# Sheet1.net
KiCad netlist of a schematic drawn in Altium Designer
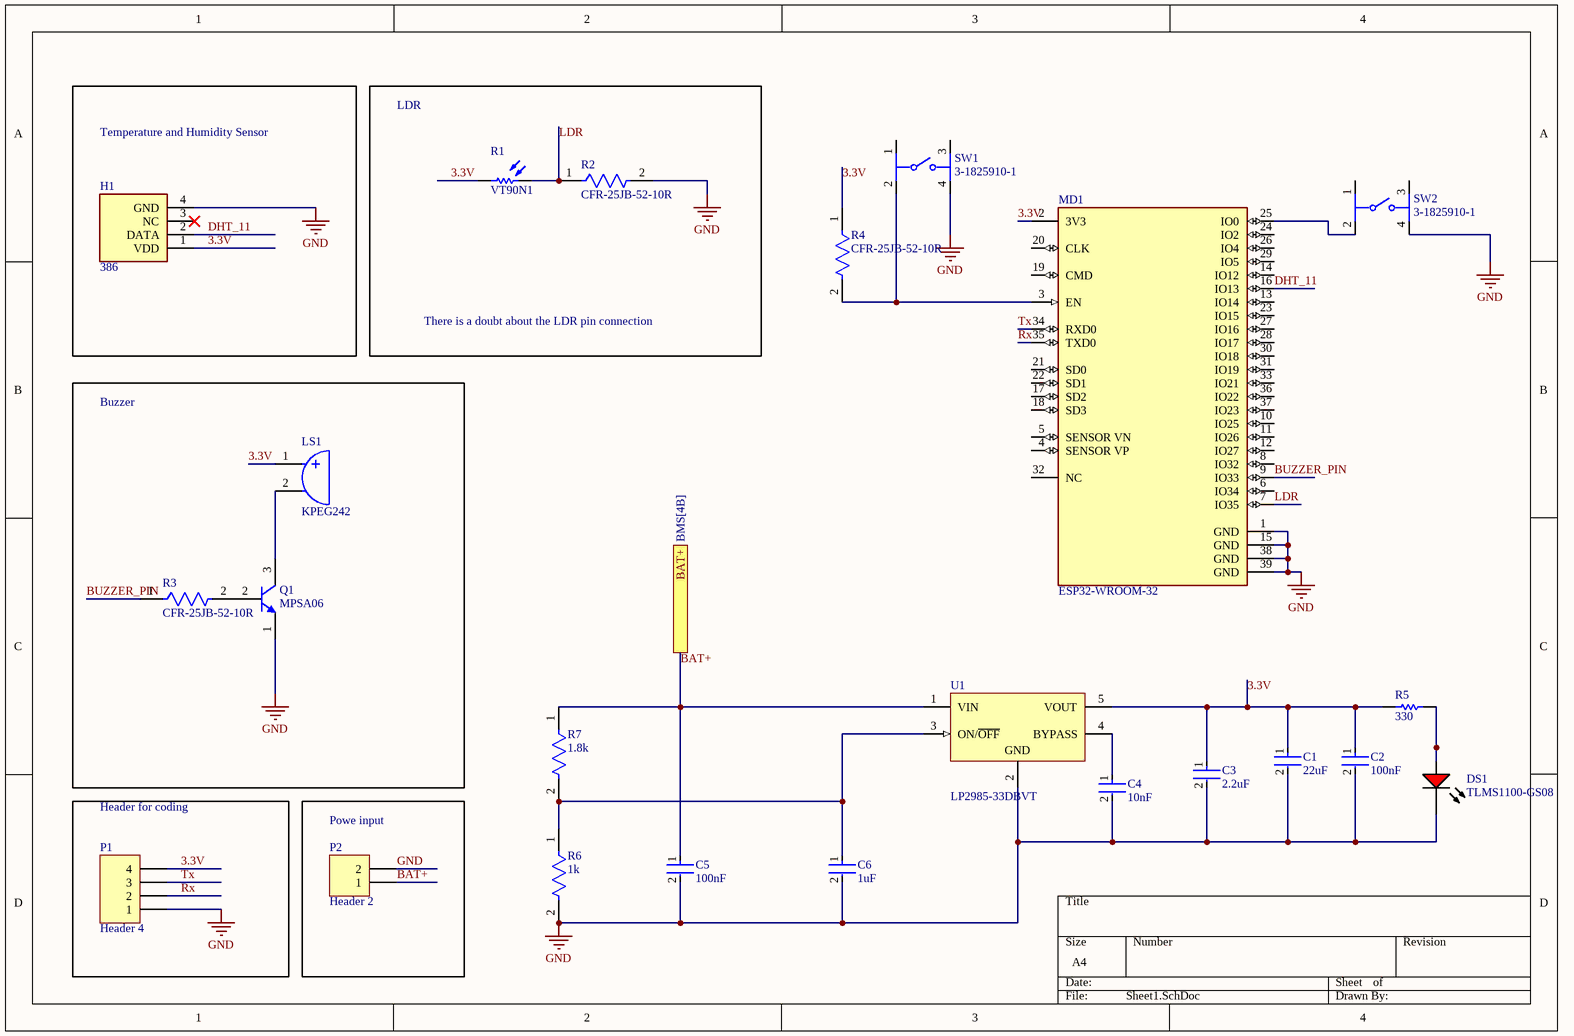
[diagram p0: Sheet1.SchDoc]

(export (version "E")
  (design (tool "Eeschema 10.0.6"))
  (components
    (comp (ref "C1")
      (value "22uF")
      (footprint "FP-GCM188-0_1-IPC_A")
      (description "Ceramic Capacitor for Automotive 100nF  ±10% 25VDC X8R 0603 Paper T/R")
      (fields (field (name "TOLERANCE") "10%"))
      (libsource (lib "Altium Content Vault") (part "02cd4be3c70576c341d710602a673aa"))
    )
    (comp (ref "C2")
      (value "100nF")
      (footprint "FP-GCM188-0_1-IPC_A")
      (description "Ceramic Capacitor for Automotive 100nF  ±10% 25VDC X8R 0603 Paper T/R")
      (fields (field (name "TOLERANCE") "10%"))
      (libsource (lib "Altium Content Vault") (part "02cd4be3c70576c341d710602a673aa"))
    )
    (comp (ref "C3")
      (value "2.2uF")
      (footprint "FP-GCM188-0_1-IPC_A")
      (description "Ceramic Capacitor for Automotive 100nF  ±10% 25VDC X8R 0603 Paper T/R")
      (fields (field (name "TOLERANCE") "10%"))
      (libsource (lib "Altium Content Vault") (part "02cd4be3c70576c341d710602a673aa"))
    )
    (comp (ref "C4")
      (value "10nF")
      (footprint "FP-GCM188-0_1-IPC_A")
      (description "Ceramic Capacitor for Automotive 100nF  ±10% 25VDC X8R 0603 Paper T/R")
      (fields (field (name "TOLERANCE") "10%"))
      (libsource (lib "Altium Content Vault") (part "02cd4be3c70576c341d710602a673aa"))
    )
    (comp (ref "C5")
      (value "100nF")
      (footprint "FP-GCM188-0_1-IPC_A")
      (description "Ceramic Capacitor for Automotive 100nF  ±10% 25VDC X8R 0603 Paper T/R")
      (fields (field (name "TOLERANCE") "10%"))
      (libsource (lib "Altium Content Vault") (part "02cd4be3c70576c341d710602a673aa"))
    )
    (comp (ref "C6")
      (value "1uF")
      (footprint "FP-GCM188-0_1-IPC_A")
      (description "Ceramic Capacitor for Automotive 100nF  ±10% 25VDC X8R 0603 Paper T/R")
      (fields (field (name "TOLERANCE") "10%"))
      (libsource (lib "Altium Content Vault") (part "02cd4be3c70576c341d710602a673aa"))
    )
    (comp (ref "DS1")
      (value "TLMS1100-GS08")
      (footprint "VISH-TLMX1100_V")
      (description "LED, RED, 2.1 V, -40 to 100 degC, 2-Pin SMD (0603), RoHS, Tape and Reel")
      (fields (field (name "TOLERANCE") "5%"))
      (libsource (lib "Altium Content Vault") (part "LED-RED-AK-2"))
    )
    (comp (ref "H1")
      (value "386")
      (footprint "SamacSys:386")
      (description "Hardware")
      (fields (field (name "MOUSER PART NUMBER") "485-386"))
      (libsource (lib "*") (part "386"))
    )
    (comp (ref "LS1")
      (value "KPEG242")
      (footprint "KINGS-KPEG242-2")
      (description "Piezo Indicator, 4100 Hz, 3 to 16 V, -20 to 70 degC, 2-Pin THD, RoHS")
      (fields (field (name "PARTNUMBER") "KPE-242") (field (name "MANUFACTURER") "KingstateElectronicsCorp."))
      (libsource (lib "Altium Content Vault") (part "KINGS-KPEG242-2"))
    )
    (comp (ref "MD1")
      (value "ESP32-WROOM-32")
      (footprint "FP-ESP32-WROOM-32-MFG")
      (description "RX TXRX MOD WIFI SURFACE MOUNT")
      (libsource (lib "Altium Content Vault") (part "ee866abf0b6c51247b7f5cdebf2f250"))
    )
    (comp (ref "P1")
      (value "Header 4")
      (footprint "HDR1X4")
      (description "Header, 4-Pin")
      (fields (field (name "PUBLISHER") "Altium Limited"))
      (libsource (lib "Miscellaneous Connectors") (part "Header 4"))
    )
    (comp (ref "P2")
      (value "Header 2")
      (footprint "HDR1X2")
      (description "Header, 2-Pin")
      (fields (field (name "PUBLISHER") "Altium Limited"))
      (libsource (lib "Miscellaneous Connectors") (part "Header 2"))
    )
    (comp (ref "Q1")
      (value "MPSA06")
      (footprint "ONSC-TO-92-3-29-11")
      (description "Amplifier Transistor, 3-Pin TO-92, Bulk Box")
      (fields (field (name "MANUFACTURER") "On Semiconductor"))
      (libsource (lib "Altium Content Vault") (part "ONSC-NPN-E1B2C3-3"))
    )
    (comp (ref "R1")
      (value "VT90N1")
      (footprint "EXCE-VT90N1")
      (description "Photoconductive Resistor, 200 kOhm, 100 V, 80 mW, -40 to 75 degC, 2-Pin THD, RoHS")
      (fields (field (name "MANUFACTURER") "Excelitas Technology"))
      (libsource (lib "Altium Content Vault") (part "PHOTO-RES-2"))
    )
    (comp (ref "R2")
      (value "CFR-25JB-52-10R")
      (footprint "FP-CFR-25-MFG")
      (description "RES 10 OHM 1/4W 5% AXIAL")
      (fields (field (name "TOLERANCE") "5%"))
      (libsource (lib "Altium Content Vault") (part "1029c3af85768c4190bb7ad29bc67b5"))
    )
    (comp (ref "R3")
      (value "CFR-25JB-52-10R")
      (footprint "FP-CFR-25-MFG")
      (description "RES 10 OHM 1/4W 5% AXIAL")
      (fields (field (name "TOLERANCE") "5%"))
      (libsource (lib "Altium Content Vault") (part "1029c3af85768c4190bb7ad29bc67b5"))
    )
    (comp (ref "R4")
      (value "CFR-25JB-52-10R")
      (footprint "FP-CFR-25-MFG")
      (description "RES 10 OHM 1/4W 5% AXIAL")
      (fields (field (name "TOLERANCE") "5%"))
      (libsource (lib "Altium Content Vault") (part "1029c3af85768c4190bb7ad29bc67b5"))
    )
    (comp (ref "R5")
      (value "330")
      (footprint "RESC1608X55X25NL10T15")
      (description "Chip Resistor, 330 Ohm, +/- 1%, 0.1 W, -55 to 155 degC, 0603 (1608 Metric), RoHS, Tape and Reel")
      (fields (field (name "TOLERANCE") "10%"))
      (libsource (lib "Altium Content Vault") (part "RES-2"))
    )
    (comp (ref "R6")
      (value "1k")
      (footprint "FP-RC0603-0_55-IPC_C")
      (description "RES SMD 1.8K OHM 1% 1/10W 0603")
      (fields (field (name "TOLERANCE") "1%"))
      (libsource (lib "Altium Content Vault") (part "1029c3af85768c4190bb7ad29bc67b5"))
    )
    (comp (ref "R7")
      (value "1.8k")
      (footprint "FP-RC0603-0_55-IPC_C")
      (description "RES SMD 1.8K OHM 1% 1/10W 0603")
      (fields (field (name "TOLERANCE") "1%"))
      (libsource (lib "Altium Content Vault") (part "1029c3af85768c4190bb7ad29bc67b5"))
    )
    (comp (ref "SW1")
      (value "3-1825910-1")
      (footprint "FP-3-1825910-1-MFG")
      (description "SWITCH TACTILE SPST-NO 0.05A 24V")
      (fields
        (field (name "MANUFACTURER") "TE Connectivity")
        (field (name "OCTOPART") "https://octopart.com/3-1825910-1-te+connectivity-46506874")
      )
      (libsource (lib "Altium Content Vault") (part "b8895f3f4cefb76e1819d2863dba89b"))
    )
    (comp (ref "SW2")
      (value "3-1825910-1")
      (footprint "FP-3-1825910-1-MFG")
      (description "SWITCH TACTILE SPST-NO 0.05A 24V")
      (fields
        (field (name "MANUFACTURER") "TE Connectivity")
        (field (name "OCTOPART") "https://octopart.com/3-1825910-1-te+connectivity-46506874")
      )
      (libsource (lib "Altium Content Vault") (part "b8895f3f4cefb76e1819d2863dba89b"))
    )
    (comp (ref "U1")
      (value "LP2985-33DBVT")
      (footprint "DBV0005A_L")
      (fields (field (name "MANUFACTURER") "Texas Instruments"))
      (libsource (lib "Altium Content Vault") (part "TI-LP2985_A-10DBV5"))
    )
  )
  (nets
    (net (code "1") (name "/3.3V") (class "Default")
      (node (ref "C1") (pin "1") (pinfunction "1_1") (pintype "passive"))
      (node (ref "C2") (pin "1") (pinfunction "1_1") (pintype "passive"))
      (node (ref "C3") (pin "1") (pinfunction "1_1") (pintype "passive"))
      (node (ref "H1") (pin "1") (pinfunction "VDD_1") (pintype "passive"))
      (node (ref "LS1") (pin "1") (pinfunction "1_1") (pintype "passive"))
      (node (ref "MD1") (pin "2") (pinfunction "3V3_2") (pintype "power_in"))
      (node (ref "P1") (pin "4") (pinfunction "4_4") (pintype "passive"))
      (node (ref "R1") (pin "1") (pinfunction "1_1") (pintype "passive"))
      (node (ref "R4") (pin "1") (pinfunction "1_1") (pintype "passive"))
      (node (ref "R5") (pin "1") (pinfunction "1_1") (pintype "passive"))
      (node (ref "U1") (pin "5") (pinfunction "VOUT_5") (pintype "power_in"))
    )
    (net (code "2") (name "/BAT+") (class "Default")
      (node (ref "C5") (pin "1") (pinfunction "1_1") (pintype "passive"))
      (node (ref "P2") (pin "1") (pinfunction "1_1") (pintype "passive"))
      (node (ref "R7") (pin "1") (pinfunction "1_1") (pintype "passive"))
      (node (ref "U1") (pin "1") (pinfunction "VIN_1") (pintype "power_in"))
    )
    (net (code "3") (name "/BUZZER_PIN") (class "Default")
      (node (ref "MD1") (pin "9") (pinfunction "IO33_9") (pintype "bidirectional"))
      (node (ref "R3") (pin "1") (pinfunction "1_1") (pintype "passive"))
    )
    (net (code "4") (name "/DHT_11") (class "Default")
      (node (ref "H1") (pin "2") (pinfunction "DATA_2") (pintype "passive"))
      (node (ref "MD1") (pin "16") (pinfunction "IO13_16") (pintype "bidirectional"))
    )
    (net (code "5") (name "/LDR") (class "Default")
      (node (ref "MD1") (pin "7") (pinfunction "IO35_7") (pintype "bidirectional"))
      (node (ref "R1") (pin "2") (pinfunction "2_2") (pintype "passive"))
      (node (ref "R2") (pin "1") (pinfunction "1_1") (pintype "passive"))
    )
    (net (code "6") (name "/Rx") (class "Default")
      (node (ref "MD1") (pin "35") (pinfunction "TXD0_35") (pintype "bidirectional"))
      (node (ref "P1") (pin "2") (pinfunction "2_2") (pintype "passive"))
    )
    (net (code "7") (name "/Tx") (class "Default")
      (node (ref "MD1") (pin "34") (pinfunction "RXD0_34") (pintype "bidirectional"))
      (node (ref "P1") (pin "3") (pinfunction "3_3") (pintype "passive"))
    )
    (net (code "8") (name "GND") (class "Default")
      (node (ref "C1") (pin "2") (pinfunction "2_2") (pintype "passive"))
      (node (ref "C2") (pin "2") (pinfunction "2_2") (pintype "passive"))
      (node (ref "C3") (pin "2") (pinfunction "2_2") (pintype "passive"))
      (node (ref "C4") (pin "2") (pinfunction "2_2") (pintype "passive"))
      (node (ref "C5") (pin "2") (pinfunction "2_2") (pintype "passive"))
      (node (ref "C6") (pin "2") (pinfunction "2_2") (pintype "passive"))
      (node (ref "DS1") (pin "2") (pinfunction "K_2") (pintype "passive"))
      (node (ref "H1") (pin "4") (pinfunction "GND_4") (pintype "passive"))
      (node (ref "MD1") (pin "1") (pinfunction "GND_1") (pintype "power_in"))
      (node (ref "MD1") (pin "15") (pinfunction "GND_15") (pintype "power_in"))
      (node (ref "MD1") (pin "38") (pinfunction "GND_38") (pintype "power_in"))
      (node (ref "MD1") (pin "39") (pinfunction "GND_39") (pintype "power_in"))
      (node (ref "P1") (pin "1") (pinfunction "1_1") (pintype "passive"))
      (node (ref "P2") (pin "2") (pinfunction "2_2") (pintype "passive"))
      (node (ref "Q1") (pin "1") (pinfunction "E_1") (pintype "passive"))
      (node (ref "R2") (pin "2") (pinfunction "2_2") (pintype "passive"))
      (node (ref "R6") (pin "2") (pinfunction "2_2") (pintype "passive"))
      (node (ref "SW1") (pin "4") (pinfunction "4_4") (pintype "passive"))
      (node (ref "SW2") (pin "4") (pinfunction "4_4") (pintype "passive"))
      (node (ref "U1") (pin "2") (pinfunction "GND_2") (pintype "power_in"))
    )
    (net (code "9") (name "Net-(DS1-A)") (class "Default")
      (node (ref "DS1") (pin "1") (pinfunction "A_1") (pintype "passive"))
      (node (ref "R5") (pin "2") (pinfunction "2_2") (pintype "passive"))
    )
    (net (code "10") (name "Net-(MD1-EN)") (class "Default")
      (node (ref "MD1") (pin "3") (pinfunction "EN_3") (pintype "input"))
      (node (ref "R4") (pin "2") (pinfunction "2_2") (pintype "passive"))
      (node (ref "SW1") (pin "2") (pinfunction "2_2") (pintype "passive"))
    )
    (net (code "11") (name "Net-(MD1-IO0)") (class "Default")
      (node (ref "MD1") (pin "25") (pinfunction "IO0_25") (pintype "bidirectional"))
      (node (ref "SW2") (pin "2") (pinfunction "2_2") (pintype "passive"))
    )
    (net (code "12") (name "Net-(Q1-B)") (class "Default")
      (node (ref "Q1") (pin "2") (pinfunction "B_2") (pintype "passive"))
      (node (ref "R3") (pin "2") (pinfunction "2_2") (pintype "passive"))
    )
    (net (code "13") (name "Net-(Q1-C)") (class "Default")
      (node (ref "LS1") (pin "2") (pinfunction "2_2") (pintype "passive"))
      (node (ref "Q1") (pin "3") (pinfunction "C_3") (pintype "passive"))
    )
    (net (code "14") (name "Net-(U1-BYPASS)") (class "Default")
      (node (ref "C4") (pin "1") (pinfunction "1_1") (pintype "passive"))
      (node (ref "U1") (pin "4") (pinfunction "BYPASS_4") (pintype "passive"))
    )
    (net (code "15") (name "Net-(U1-ON{slash}~{OFF})") (class "Default")
      (node (ref "C6") (pin "1") (pinfunction "1_1") (pintype "passive"))
      (node (ref "R6") (pin "1") (pinfunction "1_1") (pintype "passive"))
      (node (ref "R7") (pin "2") (pinfunction "2_2") (pintype "passive"))
      (node (ref "U1") (pin "3") (pinfunction "ON/~{OFF}_3") (pintype "input"))
    )
    (net (code "16") (name "unconnected-(H1-NC-Pad3)") (class "Default")
      (node (ref "H1") (pin "3") (pinfunction "NC_3") (pintype "passive+no_connect"))
    )
    (net (code "17") (name "unconnected-(MD1-CLK-Pad20)") (class "Default")
      (node (ref "MD1") (pin "20") (pinfunction "CLK_20") (pintype "bidirectional"))
    )
    (net (code "18") (name "unconnected-(MD1-CMD-Pad19)") (class "Default")
      (node (ref "MD1") (pin "19") (pinfunction "CMD_19") (pintype "bidirectional"))
    )
    (net (code "19") (name "unconnected-(MD1-IO2-Pad24)") (class "Default")
      (node (ref "MD1") (pin "24") (pinfunction "IO2_24") (pintype "bidirectional"))
    )
    (net (code "20") (name "unconnected-(MD1-IO4-Pad26)") (class "Default")
      (node (ref "MD1") (pin "26") (pinfunction "IO4_26") (pintype "bidirectional"))
    )
    (net (code "21") (name "unconnected-(MD1-IO5-Pad29)") (class "Default")
      (node (ref "MD1") (pin "29") (pinfunction "IO5_29") (pintype "bidirectional"))
    )
    (net (code "22") (name "unconnected-(MD1-IO12-Pad14)") (class "Default")
      (node (ref "MD1") (pin "14") (pinfunction "IO12_14") (pintype "bidirectional"))
    )
    (net (code "23") (name "unconnected-(MD1-IO14-Pad13)") (class "Default")
      (node (ref "MD1") (pin "13") (pinfunction "IO14_13") (pintype "bidirectional"))
    )
    (net (code "24") (name "unconnected-(MD1-IO15-Pad23)") (class "Default")
      (node (ref "MD1") (pin "23") (pinfunction "IO15_23") (pintype "bidirectional"))
    )
    (net (code "25") (name "unconnected-(MD1-IO16-Pad27)") (class "Default")
      (node (ref "MD1") (pin "27") (pinfunction "IO16_27") (pintype "bidirectional"))
    )
    (net (code "26") (name "unconnected-(MD1-IO17-Pad28)") (class "Default")
      (node (ref "MD1") (pin "28") (pinfunction "IO17_28") (pintype "bidirectional"))
    )
    (net (code "27") (name "unconnected-(MD1-IO18-Pad30)") (class "Default")
      (node (ref "MD1") (pin "30") (pinfunction "IO18_30") (pintype "bidirectional"))
    )
    (net (code "28") (name "unconnected-(MD1-IO19-Pad31)") (class "Default")
      (node (ref "MD1") (pin "31") (pinfunction "IO19_31") (pintype "bidirectional"))
    )
    (net (code "29") (name "unconnected-(MD1-IO21-Pad33)") (class "Default")
      (node (ref "MD1") (pin "33") (pinfunction "IO21_33") (pintype "bidirectional"))
    )
    (net (code "30") (name "unconnected-(MD1-IO22-Pad36)") (class "Default")
      (node (ref "MD1") (pin "36") (pinfunction "IO22_36") (pintype "bidirectional"))
    )
    (net (code "31") (name "unconnected-(MD1-IO23-Pad37)") (class "Default")
      (node (ref "MD1") (pin "37") (pinfunction "IO23_37") (pintype "bidirectional"))
    )
    (net (code "32") (name "unconnected-(MD1-IO25-Pad10)") (class "Default")
      (node (ref "MD1") (pin "10") (pinfunction "IO25_10") (pintype "bidirectional"))
    )
    (net (code "33") (name "unconnected-(MD1-IO26-Pad11)") (class "Default")
      (node (ref "MD1") (pin "11") (pinfunction "IO26_11") (pintype "bidirectional"))
    )
    (net (code "34") (name "unconnected-(MD1-IO27-Pad12)") (class "Default")
      (node (ref "MD1") (pin "12") (pinfunction "IO27_12") (pintype "bidirectional"))
    )
    (net (code "35") (name "unconnected-(MD1-IO32-Pad8)") (class "Default")
      (node (ref "MD1") (pin "8") (pinfunction "IO32_8") (pintype "bidirectional"))
    )
    (net (code "36") (name "unconnected-(MD1-IO34-Pad6)") (class "Default")
      (node (ref "MD1") (pin "6") (pinfunction "IO34_6") (pintype "bidirectional"))
    )
    (net (code "37") (name "unconnected-(MD1-NC-Pad32)") (class "Default")
      (node (ref "MD1") (pin "32") (pinfunction "NC_32") (pintype "passive"))
    )
    (net (code "38") (name "unconnected-(MD1-SD0-Pad21)") (class "Default")
      (node (ref "MD1") (pin "21") (pinfunction "SD0_21") (pintype "bidirectional"))
    )
    (net (code "39") (name "unconnected-(MD1-SD1-Pad22)") (class "Default")
      (node (ref "MD1") (pin "22") (pinfunction "SD1_22") (pintype "bidirectional"))
    )
    (net (code "40") (name "unconnected-(MD1-SD2-Pad17)") (class "Default")
      (node (ref "MD1") (pin "17") (pinfunction "SD2_17") (pintype "bidirectional"))
    )
    (net (code "41") (name "unconnected-(MD1-SD3-Pad18)") (class "Default")
      (node (ref "MD1") (pin "18") (pinfunction "SD3_18") (pintype "bidirectional"))
    )
    (net (code "42") (name "unconnected-(MD1-SENSOR_VN-Pad5)") (class "Default")
      (node (ref "MD1") (pin "5") (pinfunction "SENSOR_VN_5") (pintype "bidirectional"))
    )
    (net (code "43") (name "unconnected-(MD1-SENSOR_VP-Pad4)") (class "Default")
      (node (ref "MD1") (pin "4") (pinfunction "SENSOR_VP_4") (pintype "bidirectional"))
    )
    (net (code "44") (name "unconnected-(SW1-Pad1)") (class "Default")
      (node (ref "SW1") (pin "1") (pinfunction "1_1") (pintype "passive"))
    )
    (net (code "45") (name "unconnected-(SW1-Pad3)") (class "Default")
      (node (ref "SW1") (pin "3") (pinfunction "3_3") (pintype "passive"))
    )
    (net (code "46") (name "unconnected-(SW2-Pad1)") (class "Default")
      (node (ref "SW2") (pin "1") (pinfunction "1_1") (pintype "passive"))
    )
    (net (code "47") (name "unconnected-(SW2-Pad3)") (class "Default")
      (node (ref "SW2") (pin "3") (pinfunction "3_3") (pintype "passive"))
    )
  )
)
